# low-voltage-cutoff.net
KiCad netlist of a schematic drawn in EAGLE
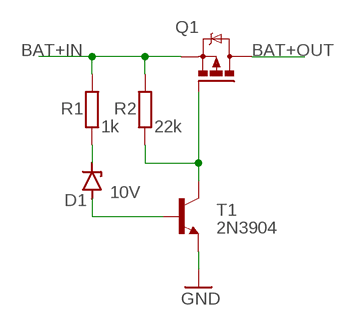
[diagram p0: schematic, sheet 1]

(export (version "E")
  (design (tool "Eeschema 10.0.6"))
  (components
    (comp (ref "D1")
      (value "10V")
      (footprint "eagle-import:DO41Z10")
      (libsource (lib "eagle-import") (part "1N4728"))
    )
    (comp (ref "Q1")
      (value "IRFU5305")
      (footprint "eagle-import:I-PAK_TO251AA")
      (libsource (lib "eagle-import") (part "IRF?5305U"))
    )
    (comp (ref "R1")
      (value "1k")
      (footprint "eagle-import:0207_10")
      (libsource (lib "eagle-import") (part "R-EU_0207/10"))
    )
    (comp (ref "R2")
      (value "22k")
      (footprint "eagle-import:0207_10")
      (libsource (lib "eagle-import") (part "R-EU_0207/10"))
    )
    (comp (ref "T1")
      (value "2N3904")
      (footprint "eagle-import:TO92")
      (libsource (lib "eagle-import") (part "2N3904"))
    )
  )
  (nets
    (net (code "1") (name "/BAT+IN") (class "Default")
      (node (ref "Q1") (pin "3") (pinfunction "S_3") (pintype "passive"))
      (node (ref "R1") (pin "2") (pinfunction "2_2") (pintype "passive"))
      (node (ref "R2") (pin "2") (pinfunction "2_2") (pintype "passive"))
    )
    (net (code "2") (name "/BAT+OUT") (class "Default")
      (node (ref "Q1") (pin "2") (pinfunction "D_2") (pintype "passive"))
    )
    (net (code "3") (name "GND") (class "Default")
      (node (ref "T1") (pin "3") (pinfunction "E_3") (pintype "passive"))
    )
    (net (code "4") (name "Net-(D1-PadC)") (class "Default")
      (node (ref "D1") (pin "C") (pinfunction "C_C") (pintype "passive"))
      (node (ref "R1") (pin "1") (pinfunction "1_1") (pintype "passive"))
    )
    (net (code "5") (name "Net-(Q1-G)") (class "Default")
      (node (ref "Q1") (pin "1") (pinfunction "G_1") (pintype "passive"))
      (node (ref "R2") (pin "1") (pinfunction "1_1") (pintype "passive"))
      (node (ref "T1") (pin "1") (pinfunction "C_1") (pintype "passive"))
    )
    (net (code "6") (name "Net-(T1-B)") (class "Default")
      (node (ref "D1") (pin "A") (pinfunction "A_A") (pintype "passive"))
      (node (ref "T1") (pin "2") (pinfunction "B_2") (pintype "passive"))
    )
  )
)
